# ALU_Ctrl.net
KiCad netlist of a schematic drawn in Altium Designer
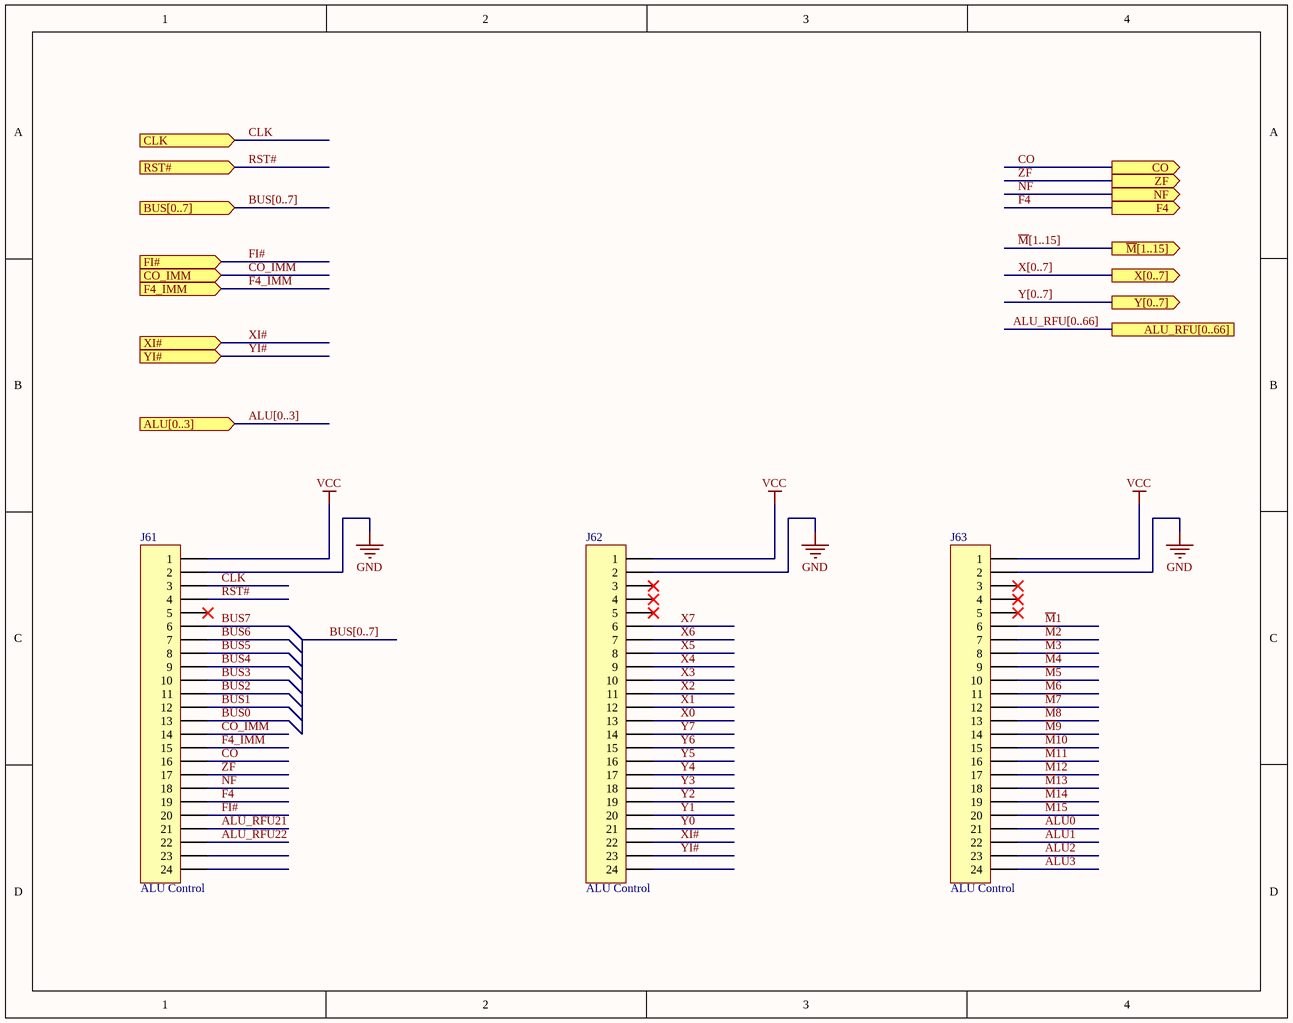
[diagram p0: ALU_Ctrl.SchDoc]

(export (version "E")
  (design (tool "Eeschema 10.0.6"))
  (components
    (comp (ref "J61")
      (value "ALU Control")
      (footprint "HDR1X24")
      (description "Header, 24-Pin")
      (fields (field (name "PUBLISHER") "Altium Limited"))
      (libsource (lib "Miscellaneous Connectors") (part "Header 24"))
    )
    (comp (ref "J62")
      (value "ALU Control")
      (footprint "HDR1X24")
      (description "Header, 24-Pin")
      (fields (field (name "PUBLISHER") "Altium Limited"))
      (libsource (lib "Miscellaneous Connectors") (part "Header 24"))
    )
    (comp (ref "J63")
      (value "ALU Control")
      (footprint "HDR1X24")
      (description "Header, 24-Pin")
      (fields (field (name "PUBLISHER") "Altium Limited"))
      (libsource (lib "Miscellaneous Connectors") (part "Header 24"))
    )
  )
  (nets
    (net (code "66") (name "/ALU0") (class "Default")
      (node (ref "J63") (pin "21") (pinfunction "21_21") (pintype "passive"))
    )
    (net (code "67") (name "/ALU1") (class "Default")
      (node (ref "J63") (pin "22") (pinfunction "22_22") (pintype "passive"))
    )
    (net (code "68") (name "/ALU2") (class "Default")
      (node (ref "J63") (pin "23") (pinfunction "23_23") (pintype "passive"))
    )
    (net (code "69") (name "/ALU3") (class "Default")
      (node (ref "J63") (pin "24") (pinfunction "24_24") (pintype "passive"))
    )
    (net (code "71") (name "/ALU_RFU21") (class "Default")
      (node (ref "J61") (pin "21") (pinfunction "21_21") (pintype "passive"))
    )
    (net (code "72") (name "/ALU_RFU22") (class "Default")
      (node (ref "J61") (pin "22") (pinfunction "22_22") (pintype "passive"))
    )
    (net (code "74") (name "/BUS0") (class "Default")
      (node (ref "J61") (pin "13") (pinfunction "13_13") (pintype "passive"))
    )
    (net (code "75") (name "/BUS1") (class "Default")
      (node (ref "J61") (pin "12") (pinfunction "12_12") (pintype "passive"))
    )
    (net (code "76") (name "/BUS2") (class "Default")
      (node (ref "J61") (pin "11") (pinfunction "11_11") (pintype "passive"))
    )
    (net (code "77") (name "/BUS3") (class "Default")
      (node (ref "J61") (pin "10") (pinfunction "10_10") (pintype "passive"))
    )
    (net (code "78") (name "/BUS4") (class "Default")
      (node (ref "J61") (pin "9") (pinfunction "9_9") (pintype "passive"))
    )
    (net (code "79") (name "/BUS5") (class "Default")
      (node (ref "J61") (pin "8") (pinfunction "8_8") (pintype "passive"))
    )
    (net (code "80") (name "/BUS6") (class "Default")
      (node (ref "J61") (pin "7") (pinfunction "7_7") (pintype "passive"))
    )
    (net (code "81") (name "/BUS7") (class "Default")
      (node (ref "J61") (pin "6") (pinfunction "6_6") (pintype "passive"))
    )
    (net (code "83") (name "/CLK") (class "Default")
      (node (ref "J61") (pin "3") (pinfunction "3_3") (pintype "passive"))
    )
    (net (code "84") (name "/CO") (class "Default")
      (node (ref "J61") (pin "16") (pinfunction "16_16") (pintype "passive"))
    )
    (net (code "85") (name "/CO_IMM") (class "Default")
      (node (ref "J61") (pin "14") (pinfunction "14_14") (pintype "passive"))
    )
    (net (code "86") (name "/F4") (class "Default")
      (node (ref "J61") (pin "19") (pinfunction "19_19") (pintype "passive"))
    )
    (net (code "87") (name "/F4_IMM") (class "Default")
      (node (ref "J61") (pin "15") (pinfunction "15_15") (pintype "passive"))
    )
    (net (code "88") (name "/FI#") (class "Default")
      (node (ref "J61") (pin "20") (pinfunction "20_20") (pintype "passive"))
    )
    (net (code "89") (name "/NF") (class "Default")
      (node (ref "J61") (pin "18") (pinfunction "18_18") (pintype "passive"))
    )
    (net (code "90") (name "/RST#") (class "Default")
      (node (ref "J61") (pin "4") (pinfunction "4_4") (pintype "passive"))
    )
    (net (code "91") (name "/X0") (class "Default")
      (node (ref "J62") (pin "13") (pinfunction "13_13") (pintype "passive"))
    )
    (net (code "92") (name "/X1") (class "Default")
      (node (ref "J62") (pin "12") (pinfunction "12_12") (pintype "passive"))
    )
    (net (code "93") (name "/X2") (class "Default")
      (node (ref "J62") (pin "11") (pinfunction "11_11") (pintype "passive"))
    )
    (net (code "94") (name "/X3") (class "Default")
      (node (ref "J62") (pin "10") (pinfunction "10_10") (pintype "passive"))
    )
    (net (code "95") (name "/X4") (class "Default")
      (node (ref "J62") (pin "9") (pinfunction "9_9") (pintype "passive"))
    )
    (net (code "96") (name "/X5") (class "Default")
      (node (ref "J62") (pin "8") (pinfunction "8_8") (pintype "passive"))
    )
    (net (code "97") (name "/X6") (class "Default")
      (node (ref "J62") (pin "7") (pinfunction "7_7") (pintype "passive"))
    )
    (net (code "98") (name "/X7") (class "Default")
      (node (ref "J62") (pin "6") (pinfunction "6_6") (pintype "passive"))
    )
    (net (code "99") (name "/XI#") (class "Default")
      (node (ref "J62") (pin "22") (pinfunction "22_22") (pintype "passive"))
    )
    (net (code "101") (name "/Y0") (class "Default")
      (node (ref "J62") (pin "21") (pinfunction "21_21") (pintype "passive"))
    )
    (net (code "102") (name "/Y1") (class "Default")
      (node (ref "J62") (pin "20") (pinfunction "20_20") (pintype "passive"))
    )
    (net (code "103") (name "/Y2") (class "Default")
      (node (ref "J62") (pin "19") (pinfunction "19_19") (pintype "passive"))
    )
    (net (code "104") (name "/Y3") (class "Default")
      (node (ref "J62") (pin "18") (pinfunction "18_18") (pintype "passive"))
    )
    (net (code "105") (name "/Y4") (class "Default")
      (node (ref "J62") (pin "17") (pinfunction "17_17") (pintype "passive"))
    )
    (net (code "106") (name "/Y5") (class "Default")
      (node (ref "J62") (pin "16") (pinfunction "16_16") (pintype "passive"))
    )
    (net (code "107") (name "/Y6") (class "Default")
      (node (ref "J62") (pin "15") (pinfunction "15_15") (pintype "passive"))
    )
    (net (code "108") (name "/Y7") (class "Default")
      (node (ref "J62") (pin "14") (pinfunction "14_14") (pintype "passive"))
    )
    (net (code "109") (name "/YI#") (class "Default")
      (node (ref "J62") (pin "23") (pinfunction "23_23") (pintype "passive"))
    )
    (net (code "111") (name "/ZF") (class "Default")
      (node (ref "J61") (pin "17") (pinfunction "17_17") (pintype "passive"))
    )
    (net (code "112") (name "/~{M}1") (class "Default")
      (node (ref "J63") (pin "6") (pinfunction "6_6") (pintype "passive"))
    )
    (net (code "113") (name "/~{M}2") (class "Default")
      (node (ref "J63") (pin "7") (pinfunction "7_7") (pintype "passive"))
    )
    (net (code "114") (name "/~{M}3") (class "Default")
      (node (ref "J63") (pin "8") (pinfunction "8_8") (pintype "passive"))
    )
    (net (code "115") (name "/~{M}4") (class "Default")
      (node (ref "J63") (pin "9") (pinfunction "9_9") (pintype "passive"))
    )
    (net (code "116") (name "/~{M}5") (class "Default")
      (node (ref "J63") (pin "10") (pinfunction "10_10") (pintype "passive"))
    )
    (net (code "117") (name "/~{M}6") (class "Default")
      (node (ref "J63") (pin "11") (pinfunction "11_11") (pintype "passive"))
    )
    (net (code "118") (name "/~{M}7") (class "Default")
      (node (ref "J63") (pin "12") (pinfunction "12_12") (pintype "passive"))
    )
    (net (code "119") (name "/~{M}8") (class "Default")
      (node (ref "J63") (pin "13") (pinfunction "13_13") (pintype "passive"))
    )
    (net (code "120") (name "/~{M}9") (class "Default")
      (node (ref "J63") (pin "14") (pinfunction "14_14") (pintype "passive"))
    )
    (net (code "121") (name "/~{M}10") (class "Default")
      (node (ref "J63") (pin "15") (pinfunction "15_15") (pintype "passive"))
    )
    (net (code "122") (name "/~{M}11") (class "Default")
      (node (ref "J63") (pin "16") (pinfunction "16_16") (pintype "passive"))
    )
    (net (code "123") (name "/~{M}12") (class "Default")
      (node (ref "J63") (pin "17") (pinfunction "17_17") (pintype "passive"))
    )
    (net (code "124") (name "/~{M}13") (class "Default")
      (node (ref "J63") (pin "18") (pinfunction "18_18") (pintype "passive"))
    )
    (net (code "125") (name "/~{M}14") (class "Default")
      (node (ref "J63") (pin "19") (pinfunction "19_19") (pintype "passive"))
    )
    (net (code "126") (name "/~{M}15") (class "Default")
      (node (ref "J63") (pin "20") (pinfunction "20_20") (pintype "passive"))
    )
    (net (code "128") (name "GND") (class "Default")
      (node (ref "J61") (pin "2") (pinfunction "2_2") (pintype "passive"))
      (node (ref "J62") (pin "2") (pinfunction "2_2") (pintype "passive"))
      (node (ref "J63") (pin "2") (pinfunction "2_2") (pintype "passive"))
    )
    (net (code "129") (name "VCC") (class "Default")
      (node (ref "J61") (pin "1") (pinfunction "1_1") (pintype "passive"))
      (node (ref "J62") (pin "1") (pinfunction "1_1") (pintype "passive"))
      (node (ref "J63") (pin "1") (pinfunction "1_1") (pintype "passive"))
    )
    (net (code "130") (name "unconnected-(J61-Pad5)") (class "Default")
      (node (ref "J61") (pin "5") (pinfunction "5_5") (pintype "passive+no_connect"))
    )
    (net (code "131") (name "unconnected-(J61-Pad23)") (class "Default")
      (node (ref "J61") (pin "23") (pinfunction "23_23") (pintype "passive"))
    )
    (net (code "132") (name "unconnected-(J61-Pad24)") (class "Default")
      (node (ref "J61") (pin "24") (pinfunction "24_24") (pintype "passive"))
    )
    (net (code "133") (name "unconnected-(J62-Pad3)") (class "Default")
      (node (ref "J62") (pin "3") (pinfunction "3_3") (pintype "passive+no_connect"))
    )
    (net (code "134") (name "unconnected-(J62-Pad4)") (class "Default")
      (node (ref "J62") (pin "4") (pinfunction "4_4") (pintype "passive+no_connect"))
    )
    (net (code "135") (name "unconnected-(J62-Pad5)") (class "Default")
      (node (ref "J62") (pin "5") (pinfunction "5_5") (pintype "passive+no_connect"))
    )
    (net (code "136") (name "unconnected-(J62-Pad24)") (class "Default")
      (node (ref "J62") (pin "24") (pinfunction "24_24") (pintype "passive"))
    )
    (net (code "137") (name "unconnected-(J63-Pad3)") (class "Default")
      (node (ref "J63") (pin "3") (pinfunction "3_3") (pintype "passive+no_connect"))
    )
    (net (code "138") (name "unconnected-(J63-Pad4)") (class "Default")
      (node (ref "J63") (pin "4") (pinfunction "4_4") (pintype "passive+no_connect"))
    )
    (net (code "139") (name "unconnected-(J63-Pad5)") (class "Default")
      (node (ref "J63") (pin "5") (pinfunction "5_5") (pintype "passive+no_connect"))
    )
  )
)
